# POWER.net
KiCad netlist of a schematic drawn in Altium Designer
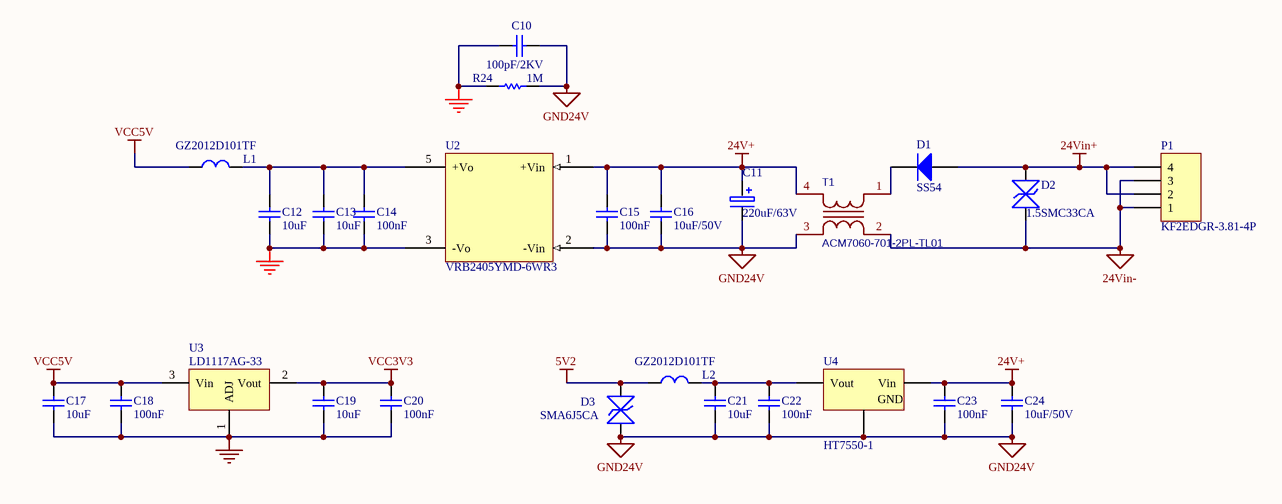
[diagram p0: POWER.SchDoc]

(export (version "E")
  (design (tool "Eeschema 10.0.6"))
  (components
    (comp (ref "C10")
      (value "100pF/2KV")
      (footprint "1206_C")
      (description "Capacitor")
      (fields (field (name "PUBLISHER") "Altium Limited"))
      (libsource (lib "Miscellaneous Devices") (part "Cap"))
    )
    (comp (ref "C11")
      (value "220uF/63V")
      (footprint "CAP-TH_BD10.0-P5.00-D1.0-FD")
      (description "Electrolytic Capacitor")
      (libsource (lib "*") (part "CD1"))
    )
    (comp (ref "C12")
      (value "10uF")
      (footprint "0805_C")
      (description "贴片电容")
      (libsource (lib "Miscellaneous Devices LC") (part "0805 10uF (106) 10% 25V"))
    )
    (comp (ref "C13")
      (value "10uF")
      (footprint "0805_C")
      (description "贴片电容")
      (libsource (lib "Miscellaneous Devices LC") (part "0805 10uF (106) 10% 25V"))
    )
    (comp (ref "C14")
      (value "100nF")
      (footprint "0805_C")
      (description "贴片电容")
      (libsource (lib "Miscellaneous Devices LC") (part "0805 100nF(104) 10% 50V"))
    )
    (comp (ref "C15")
      (value "100nF")
      (footprint "0805_C")
      (description "贴片电容")
      (libsource (lib "Miscellaneous Devices LC") (part "0805 100nF(104) 10% 50V"))
    )
    (comp (ref "C16")
      (value "10uF/50V")
      (footprint "1206_C")
      (description "贴片电容")
      (libsource (lib "Miscellaneous Devices LC") (part "1206 10uF (106) 10% 50V"))
    )
    (comp (ref "C17")
      (value "10uF")
      (footprint "0805_C")
      (description "贴片电容")
      (libsource (lib "Miscellaneous Devices LC") (part "0805 10uF (106) 10% 25V"))
    )
    (comp (ref "C18")
      (value "100nF")
      (footprint "0805_C")
      (description "贴片电容")
      (libsource (lib "Miscellaneous Devices LC") (part "0805 100nF(104) 10% 50V"))
    )
    (comp (ref "C19")
      (value "10uF")
      (footprint "0805_C")
      (description "贴片电容")
      (libsource (lib "Miscellaneous Devices LC") (part "0805 10uF (106) 10% 25V"))
    )
    (comp (ref "C20")
      (value "100nF")
      (footprint "0805_C")
      (description "贴片电容")
      (libsource (lib "Miscellaneous Devices LC") (part "0805 100nF(104) 10% 50V"))
    )
    (comp (ref "C21")
      (value "10uF")
      (footprint "0805_C")
      (description "贴片电容")
      (libsource (lib "Miscellaneous Devices LC") (part "0805 10uF (106) 10% 25V"))
    )
    (comp (ref "C22")
      (value "100nF")
      (footprint "0805_C")
      (description "贴片电容")
      (libsource (lib "Miscellaneous Devices LC") (part "0805 100nF(104) 10% 50V"))
    )
    (comp (ref "C23")
      (value "100nF")
      (footprint "0805_C")
      (description "贴片电容")
      (libsource (lib "Miscellaneous Devices LC") (part "0805 100nF(104) 10% 50V"))
    )
    (comp (ref "C24")
      (value "10uF/50V")
      (footprint "1206_C")
      (description "贴片电容")
      (libsource (lib "Miscellaneous Devices LC") (part "1206 10uF (106) 10% 50V"))
    )
    (comp (ref "D1")
      (value "SS54")
      (footprint "SMA(DO-214AC)_S1")
      (description "二极管")
      (libsource (lib "Miscellaneous Devices LC") (part "SMA(DO-214AC) SS54"))
    )
    (comp (ref "D2")
      (value "1.5SMC33CA")
      (footprint "Miscellaneous Devices LC:SMC(DO-214AB)_S1")
      (libsource (lib "IC") (part "TVS"))
    )
    (comp (ref "D3") (value "SMA6J5CA") (footprint "SMA") (libsource (lib "IC") (part "TVS")))
    (comp (ref "L1") (value "GZ2012D101TF") (footprint "0805_L") (libsource (lib "Devices") (part "L1")))
    (comp (ref "L2") (value "GZ2012D101TF") (footprint "0805_L") (libsource (lib "Devices") (part "L1")))
    (comp (ref "P1")
      (value "KF2EDGR-3.81-4P")
      (footprint "MC1.5/4-ST-3.81")
      (description "Header, 4-Pin")
      (fields (field (name "PUBLISHER") "Altium Limited"))
      (libsource (lib "Miscellaneous Connectors") (part "Header 4"))
    )
    (comp (ref "R24")
      (value "1M")
      (footprint "1206_R")
      (description "Resistor")
      (fields (field (name "PUBLISHER") "Altium Limited"))
      (libsource (lib "Miscellaneous Devices") (part "Res1"))
    )
    (comp (ref "T1")
      (value "ACM7060-701-2PL-TL01")
      (footprint "FILTER-SMD_4P-L7.0-W6.0-BL")
      (fields (field (name "BOM_SUPPLIER PART") "C78246"))
      (libsource (lib "altium-import") (part "root_0_mirrored_ACM7060-701-2PL-TL01_"))
    )
    (comp (ref "U2") (value "VRB2405YMD-6WR3") (footprint "DC/DC-1X1") (libsource (lib "*") (part "48S5")))
    (comp (ref "U3")
      (value "LD1117AG-33")
      (footprint "SOT-223")
      (description "3-Terminal Adjustable Positive Voltage Regulator")
      (libsource (lib "稳压器件") (part "LM1117"))
    )
    (comp (ref "U4")
      (value "HT7550-1")
      (footprint "SOT-89(SOT-89-3)")
      (description "低压差线性稳压(LDO)")
      (libsource (lib "Miscellaneous Devices LC") (part "SOT-89 HT7550-1"))
    )
  )
  (nets
    (net (code "1") (name "5V2") (class "Default")
      (node (ref "D3") (pin "1") (pinfunction "1_1") (pintype "passive"))
      (node (ref "L2") (pin "2") (pinfunction "2_2") (pintype "passive"))
    )
    (net (code "2") (name "24V+") (class "Default")
      (node (ref "C11") (pin "1") (pinfunction "1_1") (pintype "passive"))
      (node (ref "C15") (pin "2") (pinfunction "2_2") (pintype "passive"))
      (node (ref "C16") (pin "2") (pinfunction "2_2") (pintype "passive"))
      (node (ref "C23") (pin "2") (pinfunction "2_2") (pintype "passive"))
      (node (ref "C24") (pin "2") (pinfunction "2_2") (pintype "passive"))
      (node (ref "T1") (pin "4") (pinfunction "4_4") (pintype "passive"))
      (node (ref "U2") (pin "1") (pinfunction "+Vin_1") (pintype "input"))
      (node (ref "U4") (pin "2") (pinfunction "Vin_2") (pintype "passive"))
    )
    (net (code "3") (name "24Vin+") (class "Default")
      (node (ref "D1") (pin "1") (pinfunction "A_1") (pintype "passive"))
      (node (ref "D2") (pin "2") (pinfunction "2_2") (pintype "passive"))
      (node (ref "P1") (pin "2") (pinfunction "2_2") (pintype "passive"))
      (node (ref "P1") (pin "4") (pinfunction "4_4") (pintype "passive"))
    )
    (net (code "4") (name "24Vin-") (class "Default")
      (node (ref "D2") (pin "1") (pinfunction "1_1") (pintype "passive"))
      (node (ref "P1") (pin "1") (pinfunction "1_1") (pintype "passive"))
      (node (ref "P1") (pin "3") (pinfunction "3_3") (pintype "passive"))
      (node (ref "T1") (pin "2") (pinfunction "2_2") (pintype "passive"))
    )
    (net (code "5") (name "GND") (class "Default")
      (node (ref "C10") (pin "1") (pinfunction "1_1") (pintype "passive"))
      (node (ref "C12") (pin "1") (pinfunction "1_1") (pintype "passive"))
      (node (ref "C13") (pin "1") (pinfunction "1_1") (pintype "passive"))
      (node (ref "C14") (pin "1") (pinfunction "1_1") (pintype "passive"))
      (node (ref "C17") (pin "1") (pinfunction "1_1") (pintype "passive"))
      (node (ref "C18") (pin "1") (pinfunction "1_1") (pintype "passive"))
      (node (ref "C19") (pin "1") (pinfunction "1_1") (pintype "passive"))
      (node (ref "C20") (pin "1") (pinfunction "1_1") (pintype "passive"))
      (node (ref "R24") (pin "1") (pinfunction "1_1") (pintype "passive"))
      (node (ref "U2") (pin "3") (pinfunction "-Vo_3") (pintype "power_in"))
      (node (ref "U3") (pin "1") (pinfunction "ADJ_1") (pintype "passive"))
    )
    (net (code "6") (name "GND24V") (class "Default")
      (node (ref "C10") (pin "2") (pinfunction "2_2") (pintype "passive"))
      (node (ref "C11") (pin "2") (pinfunction "2_2") (pintype "passive"))
      (node (ref "C15") (pin "1") (pinfunction "1_1") (pintype "passive"))
      (node (ref "C16") (pin "1") (pinfunction "1_1") (pintype "passive"))
      (node (ref "C21") (pin "1") (pinfunction "1_1") (pintype "passive"))
      (node (ref "C22") (pin "1") (pinfunction "1_1") (pintype "passive"))
      (node (ref "C23") (pin "1") (pinfunction "1_1") (pintype "passive"))
      (node (ref "C24") (pin "1") (pinfunction "1_1") (pintype "passive"))
      (node (ref "D3") (pin "2") (pinfunction "2_2") (pintype "passive"))
      (node (ref "R24") (pin "2") (pinfunction "2_2") (pintype "passive"))
      (node (ref "T1") (pin "3") (pinfunction "3_3") (pintype "passive"))
      (node (ref "U2") (pin "2") (pinfunction "-Vin_2") (pintype "input"))
      (node (ref "U4") (pin "1") (pinfunction "GND_1") (pintype "passive"))
    )
    (net (code "7") (name "NC") (class "Default")
      (node (ref "U2") (pin "4") (pinfunction "NC_4") (pintype "tri_state"))
    )
    (net (code "8") (name "Net-(D1-K)") (class "Default")
      (node (ref "D1") (pin "2") (pinfunction "K_2") (pintype "passive"))
      (node (ref "T1") (pin "1") (pinfunction "1_1") (pintype "passive"))
    )
    (net (code "9") (name "Net-(U2-+Vo)") (class "Default")
      (node (ref "C12") (pin "2") (pinfunction "2_2") (pintype "passive"))
      (node (ref "C13") (pin "2") (pinfunction "2_2") (pintype "passive"))
      (node (ref "C14") (pin "2") (pinfunction "2_2") (pintype "passive"))
      (node (ref "L1") (pin "1") (pinfunction "1_1") (pintype "passive"))
      (node (ref "U2") (pin "5") (pinfunction "+Vo_5") (pintype "power_in"))
    )
    (net (code "10") (name "Net-(U4-Vout)") (class "Default")
      (node (ref "C21") (pin "2") (pinfunction "2_2") (pintype "passive"))
      (node (ref "C22") (pin "2") (pinfunction "2_2") (pintype "passive"))
      (node (ref "L2") (pin "1") (pinfunction "1_1") (pintype "passive"))
      (node (ref "U4") (pin "3") (pinfunction "Vout_3") (pintype "passive"))
    )
    (net (code "11") (name "VCC3V3") (class "Default")
      (node (ref "C19") (pin "2") (pinfunction "2_2") (pintype "passive"))
      (node (ref "C20") (pin "2") (pinfunction "2_2") (pintype "passive"))
      (node (ref "U3") (pin "2") (pinfunction "Vout_2") (pintype "passive"))
    )
    (net (code "12") (name "VCC5V") (class "Default")
      (node (ref "C17") (pin "2") (pinfunction "2_2") (pintype "passive"))
      (node (ref "C18") (pin "2") (pinfunction "2_2") (pintype "passive"))
      (node (ref "L1") (pin "2") (pinfunction "2_2") (pintype "passive"))
      (node (ref "U3") (pin "3") (pinfunction "Vin_3") (pintype "passive"))
    )
  )
)
